# Parallel_CS_V5.net
KiCad netlist of a schematic drawn in EAGLE
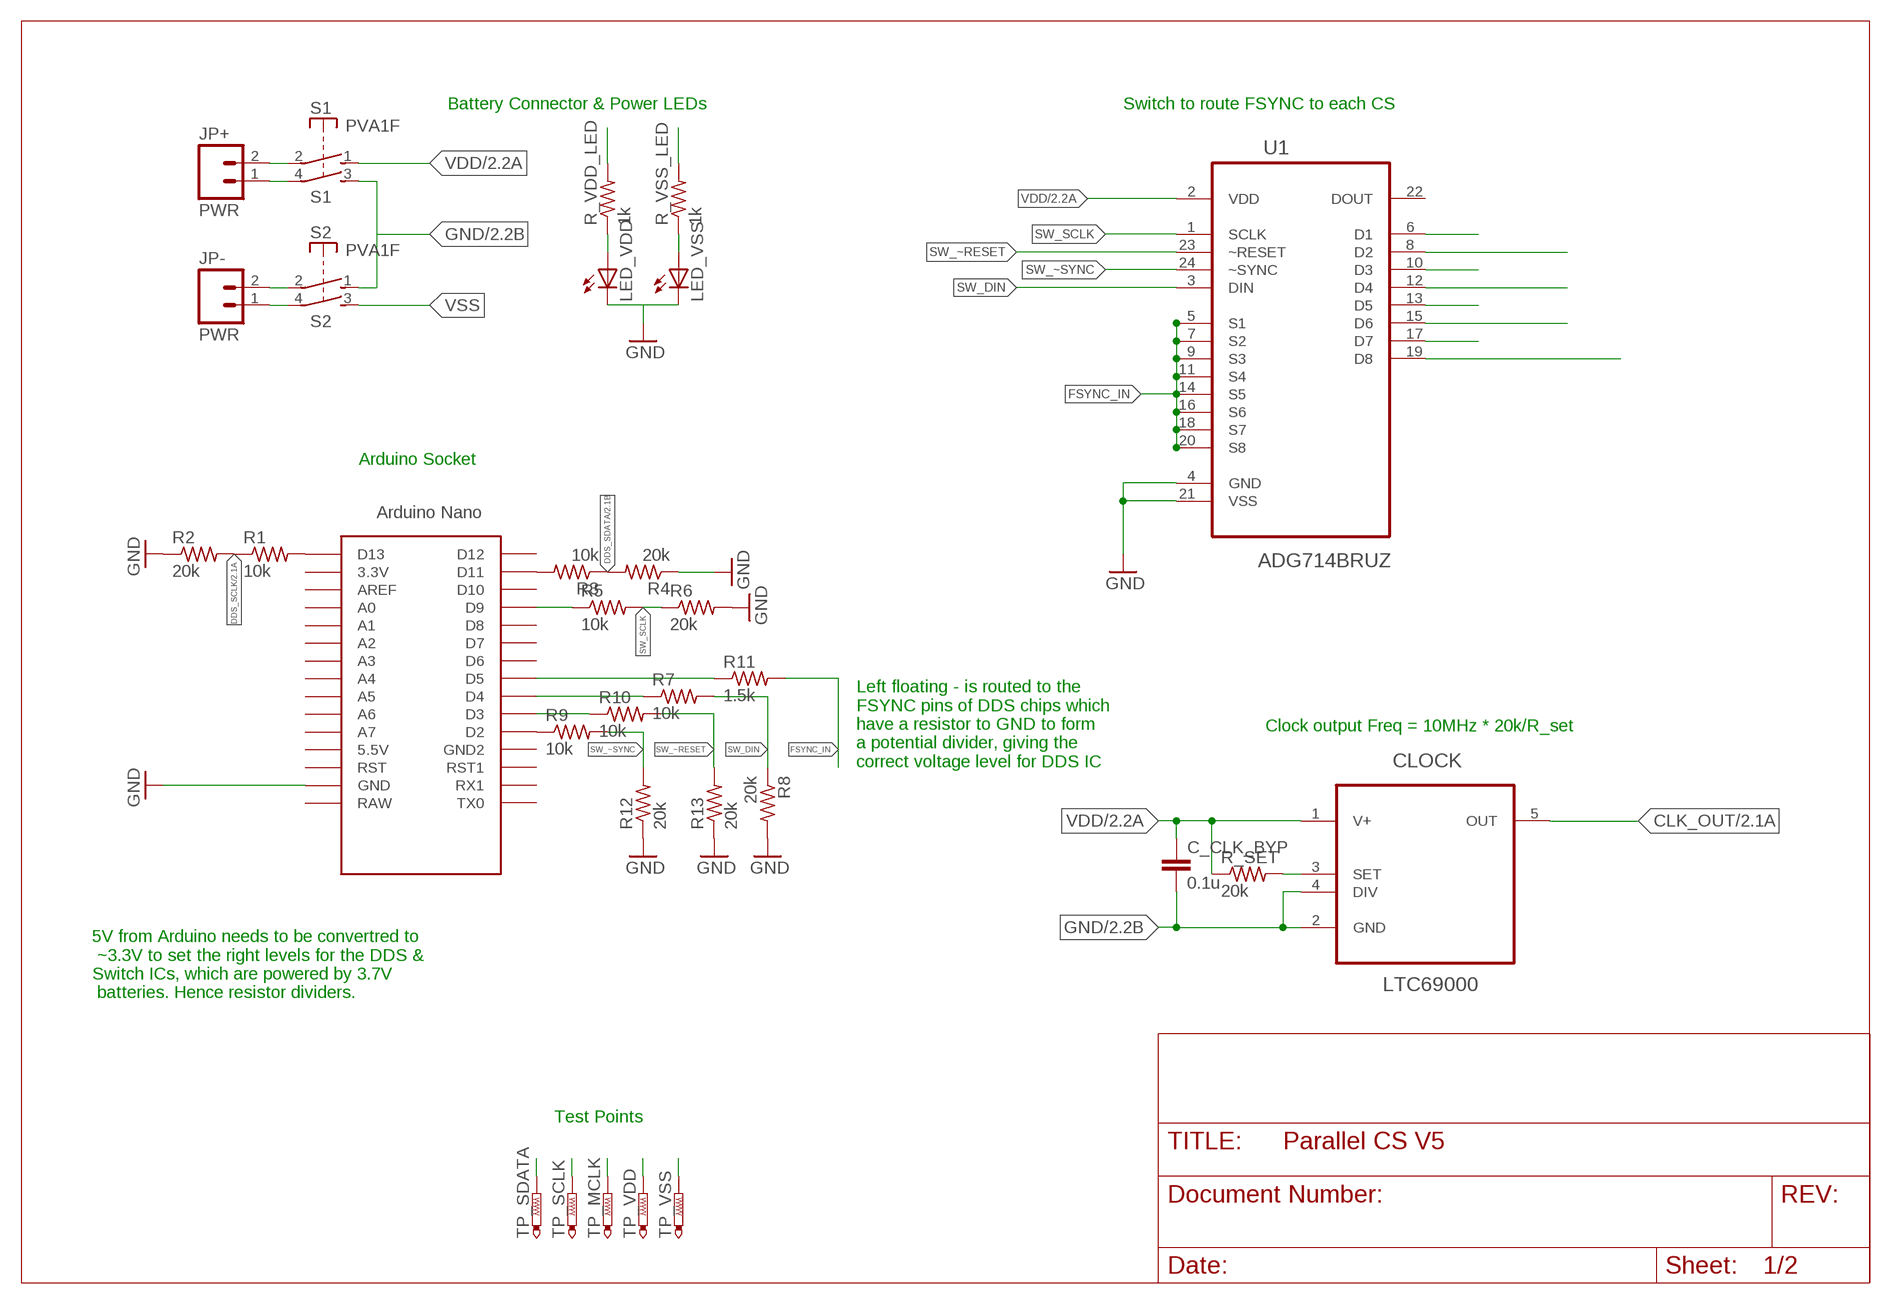
[diagram p0: schematic, sheet 1]
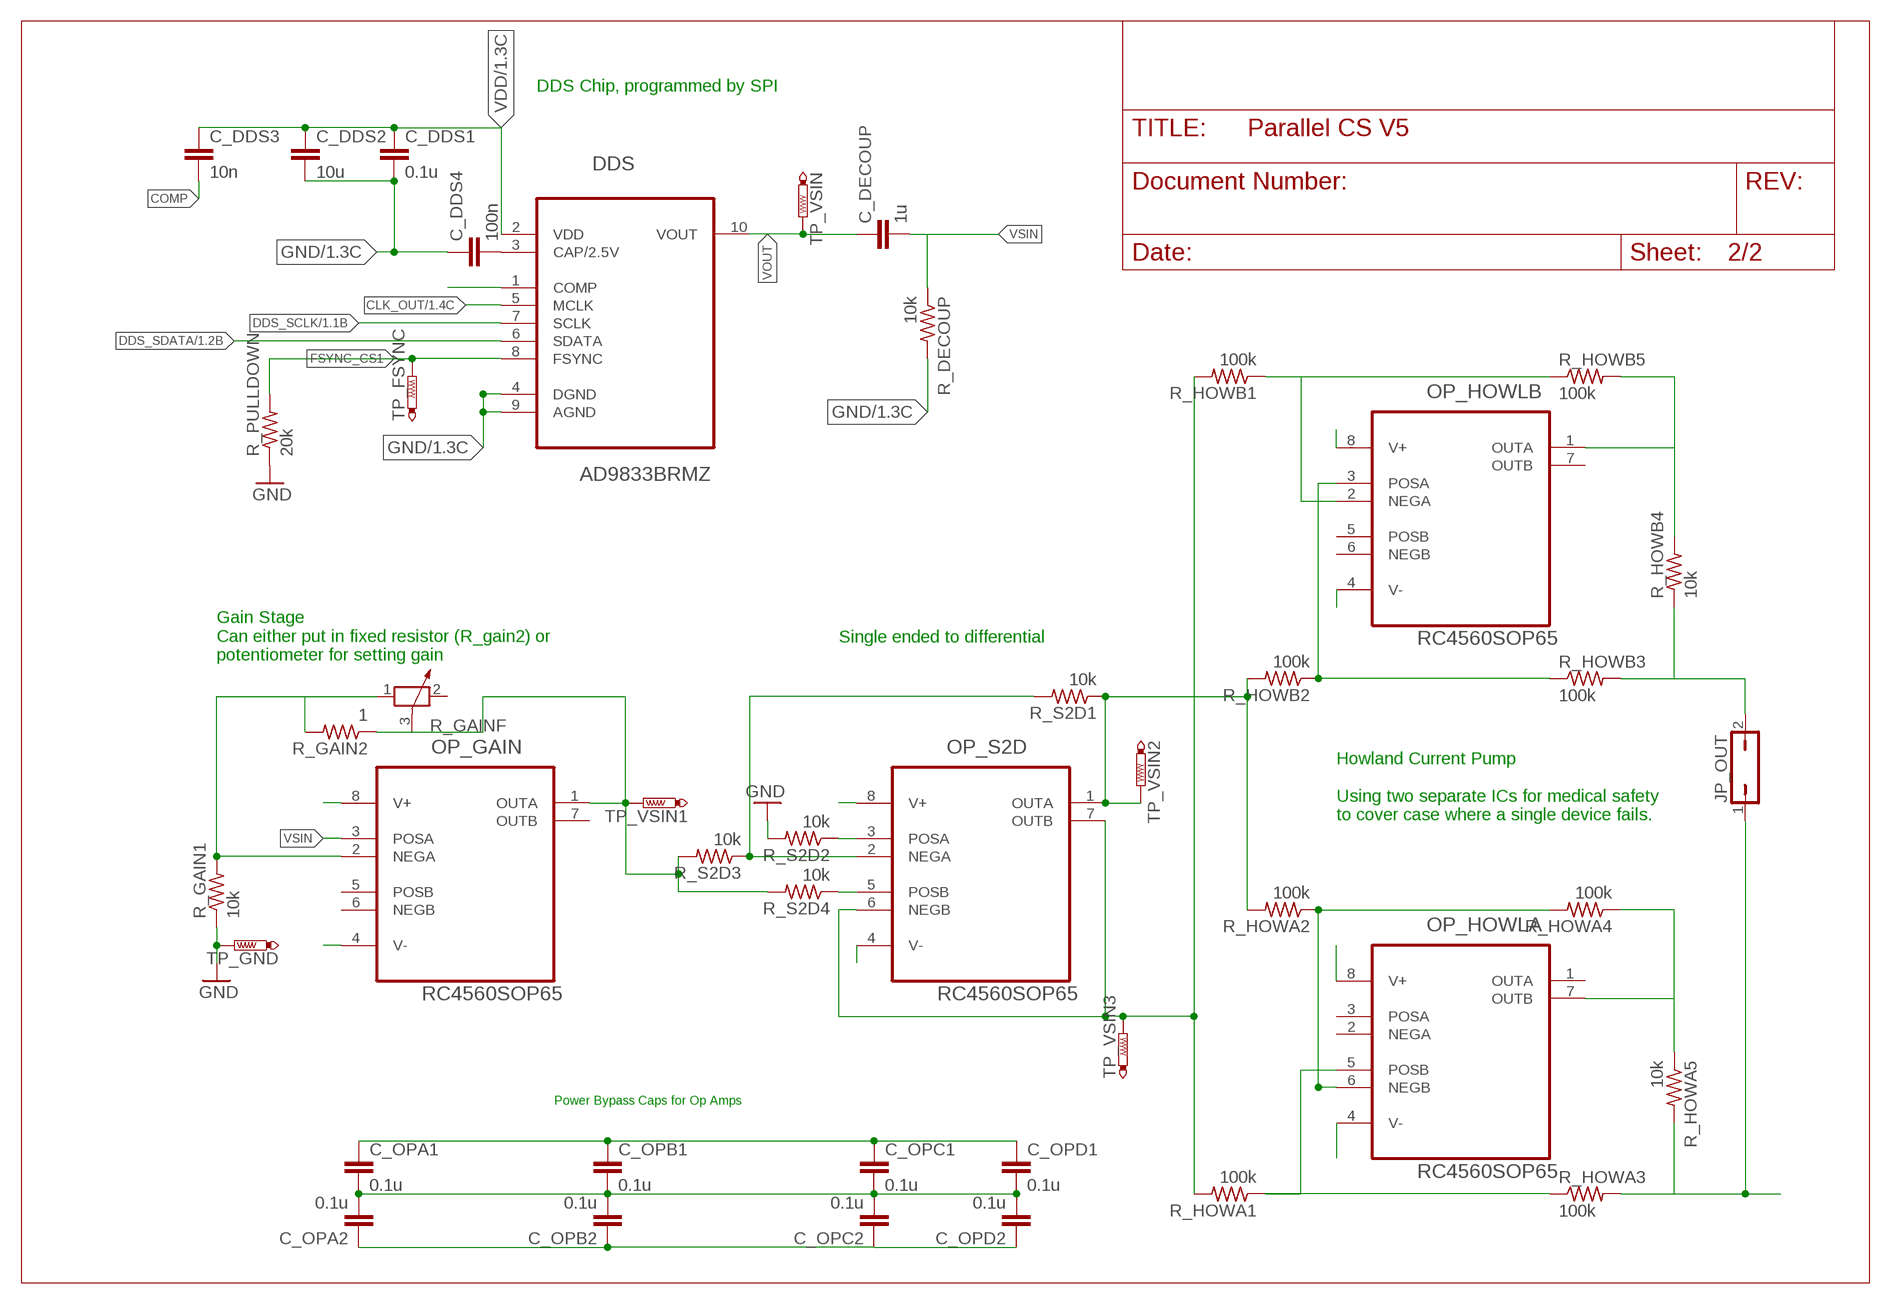
[diagram p1: schematic, sheet 2]

(export (version "E")
  (design (tool "Eeschema 10.0.6"))
  (components
    (comp (ref "C_DDS1")
      (value "0.1u")
      (footprint "eagle-import:C0805")
      (libsource (lib "eagle-import") (part "C-EUC0805"))
    )
    (comp (ref "C_DDS2")
      (value "10u")
      (footprint "eagle-import:C0805")
      (libsource (lib "eagle-import") (part "C-EUC0805"))
    )
    (comp (ref "C_DDS3")
      (value "10n")
      (footprint "eagle-import:C0805")
      (libsource (lib "eagle-import") (part "C-EUC0805"))
    )
    (comp (ref "C_DDS4")
      (value "100n")
      (footprint "eagle-import:C0805")
      (libsource (lib "eagle-import") (part "C-EUC0805"))
    )
    (comp (ref "C_DECOUP")
      (value "1u")
      (footprint "eagle-import:C0805")
      (libsource (lib "eagle-import") (part "C-EUC0805"))
    )
    (comp (ref "C_OPA1")
      (value "0.1u")
      (footprint "eagle-import:C0805")
      (libsource (lib "eagle-import") (part "C-EUC0805"))
    )
    (comp (ref "C_OPA2")
      (value "0.1u")
      (footprint "eagle-import:C0805")
      (libsource (lib "eagle-import") (part "C-EUC0805"))
    )
    (comp (ref "C_OPB1")
      (value "0.1u")
      (footprint "eagle-import:C0805")
      (libsource (lib "eagle-import") (part "C-EUC0805"))
    )
    (comp (ref "C_OPB2")
      (value "0.1u")
      (footprint "eagle-import:C0805")
      (libsource (lib "eagle-import") (part "C-EUC0805"))
    )
    (comp (ref "C_OPC1")
      (value "0.1u")
      (footprint "eagle-import:C0805")
      (libsource (lib "eagle-import") (part "C-EUC0805"))
    )
    (comp (ref "C_OPC2")
      (value "0.1u")
      (footprint "eagle-import:C0805")
      (libsource (lib "eagle-import") (part "C-EUC0805"))
    )
    (comp (ref "C_OPD1")
      (value "0.1u")
      (footprint "eagle-import:C0805")
      (libsource (lib "eagle-import") (part "C-EUC0805"))
    )
    (comp (ref "C_OPD2")
      (value "0.1u")
      (footprint "eagle-import:C0805")
      (libsource (lib "eagle-import") (part "C-EUC0805"))
    )
    (comp (ref "DDS")
      (value "AD9833BRMZ")
      (footprint "eagle-import:SOP50P490X110-10N")
      (libsource (lib "eagle-import") (part "AD9833BRMZ"))
    )
    (comp (ref "JP_OUT")
      (value "JP1Q")
      (footprint "eagle-import:JP1")
      (libsource (lib "eagle-import") (part "JP1Q"))
    )
    (comp (ref "OP_GAIN")
      (value "RC4560SOP65")
      (footprint "eagle-import:SOP65P490X109-8N")
      (libsource (lib "eagle-import") (part "RC4560SOP65"))
    )
    (comp (ref "OP_HOWLA")
      (value "RC4560SOP65")
      (footprint "eagle-import:SOP65P490X109-8N")
      (libsource (lib "eagle-import") (part "RC4560SOP65"))
    )
    (comp (ref "OP_HOWLB")
      (value "RC4560SOP65")
      (footprint "eagle-import:SOP65P490X109-8N")
      (libsource (lib "eagle-import") (part "RC4560SOP65"))
    )
    (comp (ref "OP_S2D")
      (value "RC4560SOP65")
      (footprint "eagle-import:SOP65P490X109-8N")
      (libsource (lib "eagle-import") (part "RC4560SOP65"))
    )
    (comp (ref "R_DECOUP")
      (value "10k")
      (footprint "eagle-import:R0805")
      (libsource (lib "eagle-import") (part "R-US_R0805"))
    )
    (comp (ref "R_GAIN1")
      (value "10k")
      (footprint "eagle-import:R0805")
      (libsource (lib "eagle-import") (part "R-US_R0805"))
    )
    (comp (ref "R_GAIN2")
      (value "1")
      (footprint "eagle-import:R0805")
      (libsource (lib "eagle-import") (part "R-US_R0805"))
    )
    (comp (ref "R_GAINF")
      (value "POTENTIOMETER_PT-10")
      (footprint "eagle-import:PT-10")
      (libsource (lib "eagle-import") (part "POTENTIOMETER_PT-10"))
    )
    (comp (ref "R_HOWA1")
      (value "100k")
      (footprint "eagle-import:R0805")
      (libsource (lib "eagle-import") (part "R-US_R0805"))
    )
    (comp (ref "R_HOWA2")
      (value "100k")
      (footprint "eagle-import:R0805")
      (libsource (lib "eagle-import") (part "R-US_R0805"))
    )
    (comp (ref "R_HOWA3")
      (value "100k")
      (footprint "eagle-import:R0805")
      (libsource (lib "eagle-import") (part "R-US_R0805"))
    )
    (comp (ref "R_HOWA4")
      (value "100k")
      (footprint "eagle-import:R0805")
      (libsource (lib "eagle-import") (part "R-US_R0805"))
    )
    (comp (ref "R_HOWA5")
      (value "10k")
      (footprint "eagle-import:R0805")
      (libsource (lib "eagle-import") (part "R-US_R0805"))
    )
    (comp (ref "R_HOWB1")
      (value "100k")
      (footprint "eagle-import:R0805")
      (libsource (lib "eagle-import") (part "R-US_R0805"))
    )
    (comp (ref "R_HOWB2")
      (value "100k")
      (footprint "eagle-import:R0805")
      (libsource (lib "eagle-import") (part "R-US_R0805"))
    )
    (comp (ref "R_HOWB3")
      (value "100k")
      (footprint "eagle-import:R0805")
      (libsource (lib "eagle-import") (part "R-US_R0805"))
    )
    (comp (ref "R_HOWB4")
      (value "10k")
      (footprint "eagle-import:R0805")
      (libsource (lib "eagle-import") (part "R-US_R0805"))
    )
    (comp (ref "R_HOWB5")
      (value "100k")
      (footprint "eagle-import:R0805")
      (libsource (lib "eagle-import") (part "R-US_R0805"))
    )
    (comp (ref "R_PULLDOWN")
      (value "20k")
      (footprint "eagle-import:R0805")
      (libsource (lib "eagle-import") (part "R-US_R0805"))
    )
    (comp (ref "R_S2D1")
      (value "10k")
      (footprint "eagle-import:R0805")
      (libsource (lib "eagle-import") (part "R-US_R0805"))
    )
    (comp (ref "R_S2D2")
      (value "10k")
      (footprint "eagle-import:R0805")
      (libsource (lib "eagle-import") (part "R-US_R0805"))
    )
    (comp (ref "R_S2D3")
      (value "10k")
      (footprint "eagle-import:R0805")
      (libsource (lib "eagle-import") (part "R-US_R0805"))
    )
    (comp (ref "R_S2D4")
      (value "10k")
      (footprint "eagle-import:R0805")
      (libsource (lib "eagle-import") (part "R-US_R0805"))
    )
    (comp (ref "TP_FSYNC")
      (value "PTR1PAD1-13")
      (footprint "eagle-import:P1-13")
      (libsource (lib "eagle-import") (part "PTR1PAD1-13"))
    )
    (comp (ref "TP_GND")
      (value "PTR1PAD1-13")
      (footprint "eagle-import:P1-13")
      (libsource (lib "eagle-import") (part "PTR1PAD1-13"))
    )
    (comp (ref "TP_VSIN")
      (value "PTR1PAD1-13")
      (footprint "eagle-import:P1-13")
      (libsource (lib "eagle-import") (part "PTR1PAD1-13"))
    )
    (comp (ref "TP_VSIN1")
      (value "PTR1PAD1-13")
      (footprint "eagle-import:P1-13")
      (libsource (lib "eagle-import") (part "PTR1PAD1-13"))
    )
    (comp (ref "TP_VSIN2")
      (value "PTR1PAD1-13")
      (footprint "eagle-import:P1-13")
      (libsource (lib "eagle-import") (part "PTR1PAD1-13"))
    )
    (comp (ref "TP_VSIN3")
      (value "PTR1PAD1-13")
      (footprint "eagle-import:P1-13")
      (libsource (lib "eagle-import") (part "PTR1PAD1-13"))
    )
    (comp (ref "CLOCK")
      (value "LTC69000")
      (footprint "eagle-import:SOT23-5L")
      (libsource (lib "eagle-import") (part "LTC69000"))
    )
    (comp (ref "C_CLK_BYP")
      (value "0.1u")
      (footprint "eagle-import:C0805")
      (libsource (lib "eagle-import") (part "C-EUC0805"))
    )
    (comp (ref "JP+")
      (value "PWR")
      (footprint "eagle-import:JST-2-SMD")
      (libsource (lib "eagle-import") (part "M02-JST-2MM-SMT"))
    )
    (comp (ref "JP-")
      (value "PWR")
      (footprint "eagle-import:JST-2-SMD")
      (libsource (lib "eagle-import") (part "M02-JST-2MM-SMT"))
    )
    (comp (ref "LED_VDD")
      (value "LEDSML0805")
      (footprint "eagle-import:SML0805")
      (libsource (lib "eagle-import") (part "LEDSML0805"))
    )
    (comp (ref "LED_VSS")
      (value "LEDSML0805")
      (footprint "eagle-import:SML0805")
      (libsource (lib "eagle-import") (part "LEDSML0805"))
    )
    (comp (ref "R1")
      (value "10k")
      (footprint "eagle-import:R0805")
      (libsource (lib "eagle-import") (part "resistor_R-US_R0805"))
    )
    (comp (ref "R2")
      (value "20k")
      (footprint "eagle-import:R0805")
      (libsource (lib "eagle-import") (part "resistor_R-US_R0805"))
    )
    (comp (ref "R3")
      (value "10k")
      (footprint "eagle-import:R0805")
      (libsource (lib "eagle-import") (part "resistor_R-US_R0805"))
    )
    (comp (ref "R4")
      (value "20k")
      (footprint "eagle-import:R0805")
      (libsource (lib "eagle-import") (part "resistor_R-US_R0805"))
    )
    (comp (ref "R5")
      (value "10k")
      (footprint "eagle-import:R0805")
      (libsource (lib "eagle-import") (part "resistor_R-US_R0805"))
    )
    (comp (ref "R6")
      (value "20k")
      (footprint "eagle-import:R0805")
      (libsource (lib "eagle-import") (part "resistor_R-US_R0805"))
    )
    (comp (ref "R7")
      (value "10k")
      (footprint "eagle-import:R0805")
      (libsource (lib "eagle-import") (part "resistor_R-US_R0805"))
    )
    (comp (ref "R8")
      (value "20k")
      (footprint "eagle-import:R0805")
      (libsource (lib "eagle-import") (part "resistor_R-US_R0805"))
    )
    (comp (ref "R9")
      (value "10k")
      (footprint "eagle-import:R0805")
      (libsource (lib "eagle-import") (part "resistor_R-US_R0805"))
    )
    (comp (ref "R10")
      (value "10k")
      (footprint "eagle-import:R0805")
      (libsource (lib "eagle-import") (part "resistor_R-US_R0805"))
    )
    (comp (ref "R11")
      (value "1.5k")
      (footprint "eagle-import:R0805")
      (libsource (lib "eagle-import") (part "resistor_R-US_R0805"))
    )
    (comp (ref "R12")
      (value "20k")
      (footprint "eagle-import:R0805")
      (libsource (lib "eagle-import") (part "resistor_R-US_R0805"))
    )
    (comp (ref "R13")
      (value "20k")
      (footprint "eagle-import:R0805")
      (libsource (lib "eagle-import") (part "resistor_R-US_R0805"))
    )
    (comp (ref "R_SET")
      (value "20k")
      (footprint "eagle-import:R0805")
      (libsource (lib "eagle-import") (part "resistor_R-US_R0805"))
    )
    (comp (ref "R_VDD_LED")
      (value "1k")
      (footprint "eagle-import:M0805")
      (libsource (lib "eagle-import") (part "resistor_R-US_M0805"))
    )
    (comp (ref "R_VSS_LED")
      (value "1k")
      (footprint "eagle-import:M0805")
      (libsource (lib "eagle-import") (part "resistor_R-US_M0805"))
    )
    (comp (ref "S1")
      (value "PVA1F")
      (footprint "eagle-import:PVA1F")
      (libsource (lib "eagle-import") (part "PVA1F"))
    )
    (comp (ref "S2")
      (value "PVA1F")
      (footprint "eagle-import:PVA1F")
      (libsource (lib "eagle-import") (part "PVA1F"))
    )
    (comp (ref "TP_MCLK")
      (value "PTR1PAD1-13")
      (footprint "eagle-import:P1-13")
      (libsource (lib "eagle-import") (part "PTR1PAD1-13"))
    )
    (comp (ref "TP_SCLK")
      (value "PTR1PAD1-13")
      (footprint "eagle-import:P1-13")
      (libsource (lib "eagle-import") (part "PTR1PAD1-13"))
    )
    (comp (ref "TP_SDATA")
      (value "PTR1PAD1-13")
      (footprint "eagle-import:P1-13")
      (libsource (lib "eagle-import") (part "PTR1PAD1-13"))
    )
    (comp (ref "TP_VDD")
      (value "PTR1PAD1-13")
      (footprint "eagle-import:P1-13")
      (libsource (lib "eagle-import") (part "PTR1PAD1-13"))
    )
    (comp (ref "TP_VSS")
      (value "PTR1PAD1-13")
      (footprint "eagle-import:P1-13")
      (libsource (lib "eagle-import") (part "PTR1PAD1-13"))
    )
    (comp (ref "U$1")
      (value "NANO")
      (footprint "eagle-import:NANO")
      (libsource (lib "eagle-import") (part "NANO"))
    )
    (comp (ref "U1")
      (value "ADG714BRUZ")
      (footprint "eagle-import:SOP65P640X120-24N")
      (libsource (lib "eagle-import") (part "ADG714BRUZ"))
    )
  )
  (nets
    (net (code "1") (name "CLK_OUT") (class "Default")
      (node (ref "CLOCK") (pin "5") (pinfunction "OUT_5") (pintype "output"))
      (node (ref "DDS") (pin "5") (pinfunction "MCLK_5") (pintype "input"))
      (node (ref "TP_MCLK") (pin "TP") (pinfunction "TP_TP") (pintype "input"))
    )
    (net (code "2") (name "COMP") (class "Default")
      (node (ref "C_DDS3") (pin "2") (pinfunction "2_2") (pintype "passive"))
      (node (ref "DDS") (pin "1") (pinfunction "COMP_1") (pintype "passive"))
    )
    (net (code "3") (name "DDS_SCLK") (class "Default")
      (node (ref "DDS") (pin "7") (pinfunction "SCLK_7") (pintype "input"))
      (node (ref "R1") (pin "1") (pinfunction "1_1") (pintype "passive"))
      (node (ref "R2") (pin "2") (pinfunction "2_2") (pintype "passive"))
      (node (ref "TP_SCLK") (pin "TP") (pinfunction "TP_TP") (pintype "input"))
    )
    (net (code "4") (name "DDS_SDATA") (class "Default")
      (node (ref "DDS") (pin "6") (pinfunction "SDATA_6") (pintype "input"))
      (node (ref "R3") (pin "1") (pinfunction "1_1") (pintype "passive"))
      (node (ref "R4") (pin "2") (pinfunction "2_2") (pintype "passive"))
      (node (ref "TP_SDATA") (pin "TP") (pinfunction "TP_TP") (pintype "input"))
    )
    (net (code "5") (name "FSYNC_CS1") (class "Default")
      (node (ref "DDS") (pin "8") (pinfunction "FSYNC_8") (pintype "input"))
      (node (ref "R_PULLDOWN") (pin "2") (pinfunction "2_2") (pintype "passive"))
      (node (ref "TP_FSYNC") (pin "TP") (pinfunction "TP_TP") (pintype "input"))
      (node (ref "U1") (pin "6") (pinfunction "D1_6") (pintype "bidirectional"))
    )
    (net (code "6") (name "FSYNC_IN") (class "Default")
      (node (ref "R11") (pin "2") (pinfunction "2_2") (pintype "passive"))
      (node (ref "U1") (pin "11") (pinfunction "S4_11") (pintype "bidirectional"))
      (node (ref "U1") (pin "14") (pinfunction "S5_14") (pintype "bidirectional"))
      (node (ref "U1") (pin "16") (pinfunction "S6_16") (pintype "bidirectional"))
      (node (ref "U1") (pin "18") (pinfunction "S7_18") (pintype "bidirectional"))
      (node (ref "U1") (pin "20") (pinfunction "S8_20") (pintype "bidirectional"))
      (node (ref "U1") (pin "5") (pinfunction "S1_5") (pintype "bidirectional"))
      (node (ref "U1") (pin "7") (pinfunction "S2_7") (pintype "bidirectional"))
      (node (ref "U1") (pin "9") (pinfunction "S3_9") (pintype "bidirectional"))
    )
    (net (code "7") (name "GND") (class "Default")
      (node (ref "CLOCK") (pin "2") (pinfunction "GND_2") (pintype "passive"))
      (node (ref "CLOCK") (pin "4") (pinfunction "DIV_4") (pintype "input"))
      (node (ref "C_CLK_BYP") (pin "2") (pinfunction "2_2") (pintype "passive"))
      (node (ref "C_DDS1") (pin "2") (pinfunction "2_2") (pintype "passive"))
      (node (ref "C_DDS2") (pin "2") (pinfunction "2_2") (pintype "passive"))
      (node (ref "C_DDS4") (pin "1") (pinfunction "1_1") (pintype "passive"))
      (node (ref "C_OPA1") (pin "2") (pinfunction "2_2") (pintype "passive"))
      (node (ref "C_OPA2") (pin "2") (pinfunction "2_2") (pintype "passive"))
      (node (ref "C_OPB1") (pin "2") (pinfunction "2_2") (pintype "passive"))
      (node (ref "C_OPB2") (pin "2") (pinfunction "2_2") (pintype "passive"))
      (node (ref "C_OPC1") (pin "2") (pinfunction "2_2") (pintype "passive"))
      (node (ref "C_OPC2") (pin "2") (pinfunction "2_2") (pintype "passive"))
      (node (ref "C_OPD1") (pin "2") (pinfunction "2_2") (pintype "passive"))
      (node (ref "C_OPD2") (pin "2") (pinfunction "2_2") (pintype "passive"))
      (node (ref "DDS") (pin "4") (pinfunction "DGND_4") (pintype "passive"))
      (node (ref "DDS") (pin "9") (pinfunction "AGND_9") (pintype "passive"))
      (node (ref "LED_VDD") (pin "C") (pinfunction "C_C") (pintype "passive"))
      (node (ref "LED_VSS") (pin "C") (pinfunction "C_C") (pintype "passive"))
      (node (ref "R12") (pin "1") (pinfunction "1_1") (pintype "passive"))
      (node (ref "R13") (pin "1") (pinfunction "1_1") (pintype "passive"))
      (node (ref "R2") (pin "1") (pinfunction "1_1") (pintype "passive"))
      (node (ref "R4") (pin "1") (pinfunction "1_1") (pintype "passive"))
      (node (ref "R6") (pin "2") (pinfunction "2_2") (pintype "passive"))
      (node (ref "R8") (pin "2") (pinfunction "2_2") (pintype "passive"))
      (node (ref "R_DECOUP") (pin "2") (pinfunction "2_2") (pintype "passive"))
      (node (ref "R_GAIN1") (pin "1") (pinfunction "1_1") (pintype "passive"))
      (node (ref "R_PULLDOWN") (pin "1") (pinfunction "1_1") (pintype "passive"))
      (node (ref "R_S2D2") (pin "2") (pinfunction "2_2") (pintype "passive"))
      (node (ref "S1") (pin "3") (pinfunction "S_3") (pintype "passive"))
      (node (ref "S2") (pin "1") (pinfunction "S_1") (pintype "passive"))
      (node (ref "TP_GND") (pin "TP") (pinfunction "TP_TP") (pintype "input"))
      (node (ref "U$1") (pin "GND") (pinfunction "GND_GND") (pintype "bidirectional"))
      (node (ref "U1") (pin "21") (pinfunction "VSS_21") (pintype "power_in"))
      (node (ref "U1") (pin "4") (pinfunction "GND_4") (pintype "passive"))
    )
    (net (code "8") (name "Net-(CLOCK-SET)") (class "Default")
      (node (ref "CLOCK") (pin "3") (pinfunction "SET_3") (pintype "input"))
      (node (ref "R_SET") (pin "2") (pinfunction "2_2") (pintype "passive"))
    )
    (net (code "9") (name "Net-(DDS-CAP{slash}2.5V)") (class "Default")
      (node (ref "C_DDS4") (pin "2") (pinfunction "2_2") (pintype "passive"))
      (node (ref "DDS") (pin "3") (pinfunction "CAP/2.5V_3") (pintype "passive"))
    )
    (net (code "10") (name "Net-(JP_OUT-Pad1)") (class "Default")
      (node (ref "JP_OUT") (pin "1") (pinfunction "1_1") (pintype "passive"))
      (node (ref "R_HOWA3") (pin "2") (pinfunction "2_2") (pintype "passive"))
      (node (ref "R_HOWA5") (pin "2") (pinfunction "2_2") (pintype "passive"))
    )
    (net (code "11") (name "Net-(JP_OUT-Pad2)") (class "Default")
      (node (ref "JP_OUT") (pin "2") (pinfunction "2_2") (pintype "passive"))
      (node (ref "R_HOWB3") (pin "2") (pinfunction "2_2") (pintype "passive"))
      (node (ref "R_HOWB4") (pin "1") (pinfunction "1_1") (pintype "passive"))
    )
    (net (code "12") (name "Net-(LED_VDD-PadA)") (class "Default")
      (node (ref "LED_VDD") (pin "A") (pinfunction "A_A") (pintype "passive"))
      (node (ref "R_VDD_LED") (pin "1") (pinfunction "1_1") (pintype "passive"))
    )
    (net (code "13") (name "Net-(LED_VSS-PadA)") (class "Default")
      (node (ref "LED_VSS") (pin "A") (pinfunction "A_A") (pintype "passive"))
      (node (ref "R_VSS_LED") (pin "1") (pinfunction "1_1") (pintype "passive"))
    )
    (net (code "14") (name "Net-(OP_GAIN-NEGA)") (class "Default")
      (node (ref "OP_GAIN") (pin "2") (pinfunction "NEGA_2") (pintype "input"))
      (node (ref "R_GAIN1") (pin "2") (pinfunction "2_2") (pintype "passive"))
      (node (ref "R_GAIN2") (pin "2") (pinfunction "2_2") (pintype "passive"))
      (node (ref "R_GAINF") (pin "1") (pinfunction "1_1") (pintype "passive"))
    )
    (net (code "15") (name "Net-(OP_GAIN-OUTA)") (class "Default")
      (node (ref "OP_GAIN") (pin "1") (pinfunction "OUTA_1") (pintype "output"))
      (node (ref "R_GAIN2") (pin "1") (pinfunction "1_1") (pintype "passive"))
      (node (ref "R_GAINF") (pin "3") (pinfunction "3_3") (pintype "passive"))
      (node (ref "R_S2D3") (pin "2") (pinfunction "2_2") (pintype "passive"))
      (node (ref "R_S2D4") (pin "2") (pinfunction "2_2") (pintype "passive"))
      (node (ref "TP_VSIN1") (pin "TP") (pinfunction "TP_TP") (pintype "input"))
    )
    (net (code "16") (name "Net-(OP_HOWLA-NEGB)") (class "Default")
      (node (ref "OP_HOWLA") (pin "6") (pinfunction "NEGB_6") (pintype "input"))
      (node (ref "R_HOWA2") (pin "1") (pinfunction "1_1") (pintype "passive"))
      (node (ref "R_HOWA4") (pin "2") (pinfunction "2_2") (pintype "passive"))
    )
    (net (code "17") (name "Net-(OP_HOWLA-OUTB)") (class "Default")
      (node (ref "OP_HOWLA") (pin "7") (pinfunction "OUTB_7") (pintype "output"))
      (node (ref "R_HOWA4") (pin "1") (pinfunction "1_1") (pintype "passive"))
      (node (ref "R_HOWA5") (pin "1") (pinfunction "1_1") (pintype "passive"))
    )
    (net (code "18") (name "Net-(OP_HOWLA-POSB)") (class "Default")
      (node (ref "OP_HOWLA") (pin "5") (pinfunction "POSB_5") (pintype "input"))
      (node (ref "R_HOWA1") (pin "1") (pinfunction "1_1") (pintype "passive"))
      (node (ref "R_HOWA3") (pin "1") (pinfunction "1_1") (pintype "passive"))
    )
    (net (code "19") (name "Net-(OP_HOWLB-NEGA)") (class "Default")
      (node (ref "OP_HOWLB") (pin "2") (pinfunction "NEGA_2") (pintype "input"))
      (node (ref "R_HOWB1") (pin "1") (pinfunction "1_1") (pintype "passive"))
      (node (ref "R_HOWB5") (pin "1") (pinfunction "1_1") (pintype "passive"))
    )
    (net (code "20") (name "Net-(OP_HOWLB-OUTA)") (class "Default")
      (node (ref "OP_HOWLB") (pin "1") (pinfunction "OUTA_1") (pintype "output"))
      (node (ref "R_HOWB4") (pin "2") (pinfunction "2_2") (pintype "passive"))
      (node (ref "R_HOWB5") (pin "2") (pinfunction "2_2") (pintype "passive"))
    )
    (net (code "21") (name "Net-(OP_HOWLB-POSA)") (class "Default")
      (node (ref "OP_HOWLB") (pin "3") (pinfunction "POSA_3") (pintype "input"))
      (node (ref "R_HOWB2") (pin "1") (pinfunction "1_1") (pintype "passive"))
      (node (ref "R_HOWB3") (pin "1") (pinfunction "1_1") (pintype "passive"))
    )
    (net (code "22") (name "Net-(OP_S2D-NEGA)") (class "Default")
      (node (ref "OP_S2D") (pin "2") (pinfunction "NEGA_2") (pintype "input"))
      (node (ref "R_S2D1") (pin "2") (pinfunction "2_2") (pintype "passive"))
      (node (ref "R_S2D3") (pin "1") (pinfunction "1_1") (pintype "passive"))
    )
    (net (code "23") (name "Net-(OP_S2D-NEGB)") (class "Default")
      (node (ref "OP_S2D") (pin "6") (pinfunction "NEGB_6") (pintype "input"))
      (node (ref "OP_S2D") (pin "7") (pinfunction "OUTB_7") (pintype "output"))
      (node (ref "R_HOWA1") (pin "2") (pinfunction "2_2") (pintype "passive"))
      (node (ref "R_HOWB1") (pin "2") (pinfunction "2_2") (pintype "passive"))
      (node (ref "TP_VSIN3") (pin "TP") (pinfunction "TP_TP") (pintype "input"))
    )
    (net (code "24") (name "Net-(OP_S2D-OUTA)") (class "Default")
      (node (ref "OP_S2D") (pin "1") (pinfunction "OUTA_1") (pintype "output"))
      (node (ref "R_HOWA2") (pin "2") (pinfunction "2_2") (pintype "passive"))
      (node (ref "R_HOWB2") (pin "2") (pinfunction "2_2") (pintype "passive"))
      (node (ref "R_S2D1") (pin "1") (pinfunction "1_1") (pintype "passive"))
      (node (ref "TP_VSIN2") (pin "TP") (pinfunction "TP_TP") (pintype "input"))
    )
    (net (code "25") (name "Net-(OP_S2D-POSA)") (class "Default")
      (node (ref "OP_S2D") (pin "3") (pinfunction "POSA_3") (pintype "input"))
      (node (ref "R_S2D2") (pin "1") (pinfunction "1_1") (pintype "passive"))
    )
    (net (code "26") (name "Net-(OP_S2D-POSB)") (class "Default")
      (node (ref "OP_S2D") (pin "5") (pinfunction "POSB_5") (pintype "input"))
      (node (ref "R_S2D4") (pin "1") (pinfunction "1_1") (pintype "passive"))
    )
    (net (code "27") (name "Net-(R1-Pad2)") (class "Default")
      (node (ref "R1") (pin "2") (pinfunction "2_2") (pintype "passive"))
      (node (ref "U$1") (pin "D13") (pinfunction "D13_D13") (pintype "bidirectional"))
    )
    (net (code "28") (name "Net-(R3-Pad2)") (class "Default")
      (node (ref "R3") (pin "2") (pinfunction "2_2") (pintype "passive"))
      (node (ref "U$1") (pin "D11") (pinfunction "D11_D11") (pintype "bidirectional"))
    )
    (net (code "29") (name "Net-(R5-Pad1)") (class "Default")
      (node (ref "R5") (pin "1") (pinfunction "1_1") (pintype "passive"))
      (node (ref "U$1") (pin "D9") (pinfunction "D9_D9") (pintype "bidirectional"))
    )
    (net (code "30") (name "Net-(R7-Pad1)") (class "Default")
      (node (ref "R7") (pin "1") (pinfunction "1_1") (pintype "passive"))
      (node (ref "U$1") (pin "D4") (pinfunction "D4_D4") (pintype "bidirectional"))
    )
    (net (code "31") (name "Net-(R9-Pad1)") (class "Default")
      (node (ref "R9") (pin "1") (pinfunction "1_1") (pintype "passive"))
      (node (ref "U$1") (pin "D2") (pinfunction "D2_D2") (pintype "bidirectional"))
    )
    (net (code "32") (name "Net-(R10-Pad1)") (class "Default")
      (node (ref "R10") (pin "1") (pinfunction "1_1") (pintype "passive"))
      (node (ref "U$1") (pin "D3") (pinfunction "D3_D3") (pintype "bidirectional"))
    )
    (net (code "33") (name "Net-(R11-Pad1)") (class "Default")
      (node (ref "R11") (pin "1") (pinfunction "1_1") (pintype "passive"))
      (node (ref "U$1") (pin "D5") (pinfunction "D5_D5") (pintype "bidirectional"))
    )
    (net (code "34") (name "Net-(S1A-P)") (class "Default")
      (node (ref "JP+") (pin "2") (pinfunction "2_2") (pintype "passive"))
      (node (ref "S1") (pin "2") (pinfunction "P_2") (pintype "passive"))
    )
    (net (code "35") (name "Net-(S1B-P)") (class "Default")
      (node (ref "JP+") (pin "1") (pinfunction "1_1") (pintype "passive"))
      (node (ref "S1") (pin "4") (pinfunction "P_4") (pintype "passive"))
    )
    (net (code "36") (name "Net-(S2A-P)") (class "Default")
      (node (ref "JP-") (pin "2") (pinfunction "2_2") (pintype "passive"))
      (node (ref "S2") (pin "2") (pinfunction "P_2") (pintype "passive"))
    )
    (net (code "37") (name "Net-(S2B-P)") (class "Default")
      (node (ref "JP-") (pin "1") (pinfunction "1_1") (pintype "passive"))
      (node (ref "S2") (pin "4") (pinfunction "P_4") (pintype "passive"))
    )
    (net (code "38") (name "SW_DIN") (class "Default")
      (node (ref "R7") (pin "2") (pinfunction "2_2") (pintype "passive"))
      (node (ref "R8") (pin "1") (pinfunction "1_1") (pintype "passive"))
      (node (ref "U1") (pin "3") (pinfunction "DIN_3") (pintype "input"))
    )
    (net (code "39") (name "SW_SCLK") (class "Default")
      (node (ref "R5") (pin "2") (pinfunction "2_2") (pintype "passive"))
      (node (ref "R6") (pin "1") (pinfunction "1_1") (pintype "passive"))
      (node (ref "U1") (pin "1") (pinfunction "SCLK_1") (pintype "input"))
    )
    (net (code "40") (name "SW_~{RESET}") (class "Default")
      (node (ref "R10") (pin "2") (pinfunction "2_2") (pintype "passive"))
      (node (ref "R13") (pin "2") (pinfunction "2_2") (pintype "passive"))
      (node (ref "U1") (pin "23") (pinfunction "~{RESET}_23") (pintype "input"))
    )
    (net (code "41") (name "SW_~{SYNC}") (class "Default")
      (node (ref "R12") (pin "2") (pinfunction "2_2") (pintype "passive"))
      (node (ref "R9") (pin "2") (pinfunction "2_2") (pintype "passive"))
      (node (ref "U1") (pin "24") (pinfunction "~{SYNC}_24") (pintype "input"))
    )
    (net (code "42") (name "VDD") (class "Default")
      (node (ref "CLOCK") (pin "1") (pinfunction "V+_1") (pintype "power_in"))
      (node (ref "C_CLK_BYP") (pin "1") (pinfunction "1_1") (pintype "passive"))
      (node (ref "C_DDS1") (pin "1") (pinfunction "1_1") (pintype "passive"))
      (node (ref "C_DDS2") (pin "1") (pinfunction "1_1") (pintype "passive"))
      (node (ref "C_DDS3") (pin "1") (pinfunction "1_1") (pintype "passive"))
      (node (ref "C_OPA1") (pin "1") (pinfunction "1_1") (pintype "passive"))
      (node (ref "C_OPB1") (pin "1") (pinfunction "1_1") (pintype "passive"))
      (node (ref "C_OPC1") (pin "1") (pinfunction "1_1") (pintype "passive"))
      (node (ref "C_OPD1") (pin "1") (pinfunction "1_1") (pintype "passive"))
      (node (ref "DDS") (pin "2") (pinfunction "VDD_2") (pintype "power_in"))
      (node (ref "OP_GAIN") (pin "8") (pinfunction "V+_8") (pintype "power_in"))
      (node (ref "OP_HOWLA") (pin "8") (pinfunction "V+_8") (pintype "power_in"))
      (node (ref "OP_HOWLB") (pin "8") (pinfunction "V+_8") (pintype "power_in"))
      (node (ref "OP_S2D") (pin "8") (pinfunction "V+_8") (pintype "power_in"))
      (node (ref "R_SET") (pin "1") (pinfunction "1_1") (pintype "passive"))
      (node (ref "R_VDD_LED") (pin "2") (pinfunction "2_2") (pintype "passive"))
      (node (ref "S1") (pin "1") (pinfunction "S_1") (pintype "passive"))
      (node (ref "TP_VDD") (pin "TP") (pinfunction "TP_TP") (pintype "input"))
      (node (ref "U1") (pin "2") (pinfunction "VDD_2") (pintype "power_in"))
    )
    (net (code "43") (name "VOUT") (class "Default")
      (node (ref "C_DECOUP") (pin "1") (pinfunction "1_1") (pintype "passive"))
      (node (ref "DDS") (pin "10") (pinfunction "VOUT_10") (pintype "output"))
      (node (ref "TP_VSIN") (pin "TP") (pinfunction "TP_TP") (pintype "input"))
    )
    (net (code "44") (name "VSIN") (class "Default")
      (node (ref "C_DECOUP") (pin "2") (pinfunction "2_2") (pintype "passive"))
      (node (ref "OP_GAIN") (pin "3") (pinfunction "POSA_3") (pintype "input"))
      (node (ref "R_DECOUP") (pin "1") (pinfunction "1_1") (pintype "passive"))
    )
    (net (code "45") (name "VSS") (class "Default")
      (node (ref "C_OPA2") (pin "1") (pinfunction "1_1") (pintype "passive"))
      (node (ref "C_OPB2") (pin "1") (pinfunction "1_1") (pintype "passive"))
      (node (ref "C_OPC2") (pin "1") (pinfunction "1_1") (pintype "passive"))
      (node (ref "C_OPD2") (pin "1") (pinfunction "1_1") (pintype "passive"))
      (node (ref "OP_GAIN") (pin "4") (pinfunction "V-_4") (pintype "power_in"))
      (node (ref "OP_HOWLA") (pin "4") (pinfunction "V-_4") (pintype "power_in"))
      (node (ref "OP_HOWLB") (pin "4") (pinfunction "V-_4") (pintype "power_in"))
      (node (ref "OP_S2D") (pin "4") (pinfunction "V-_4") (pintype "power_in"))
      (node (ref "R_VSS_LED") (pin "2") (pinfunction "2_2") (pintype "passive"))
      (node (ref "S2") (pin "3") (pinfunction "S_3") (pintype "passive"))
      (node (ref "TP_VSS") (pin "TP") (pinfunction "TP_TP") (pintype "input"))
    )
    (net (code "46") (name "unconnected-(OP_GAIN-NEGB-Pad6)") (class "Default")
      (node (ref "OP_GAIN") (pin "6") (pinfunction "NEGB_6") (pintype "input"))
    )
    (net (code "47") (name "unconnected-(OP_GAIN-OUTB-Pad7)") (class "Default")
      (node (ref "OP_GAIN") (pin "7") (pinfunction "OUTB_7") (pintype "output"))
    )
    (net (code "48") (name "unconnected-(OP_GAIN-POSB-Pad5)") (class "Default")
      (node (ref "OP_GAIN") (pin "5") (pinfunction "POSB_5") (pintype "input"))
    )
    (net (code "49") (name "unconnected-(OP_HOWLA-NEGA-Pad2)") (class "Default")
      (node (ref "OP_HOWLA") (pin "2") (pinfunction "NEGA_2") (pintype "input"))
    )
    (net (code "50") (name "unconnected-(OP_HOWLA-OUTA-Pad1)") (class "Default")
      (node (ref "OP_HOWLA") (pin "1") (pinfunction "OUTA_1") (pintype "output"))
    )
    (net (code "51") (name "unconnected-(OP_HOWLA-POSA-Pad3)") (class "Default")
      (node (ref "OP_HOWLA") (pin "3") (pinfunction "POSA_3") (pintype "input"))
    )
    (net (code "52") (name "unconnected-(OP_HOWLB-NEGB-Pad6)") (class "Default")
      (node (ref "OP_HOWLB") (pin "6") (pinfunction "NEGB_6") (pintype "input"))
    )
    (net (code "53") (name "unconnected-(OP_HOWLB-OUTB-Pad7)") (class "Default")
      (node (ref "OP_HOWLB") (pin "7") (pinfunction "OUTB_7") (pintype "output"))
    )
    (net (code "54") (name "unconnected-(OP_HOWLB-POSB-Pad5)") (class "Default")
      (node (ref "OP_HOWLB") (pin "5") (pinfunction "POSB_5") (pintype "input"))
    )
    (net (code "55") (name "unconnected-(R_GAINF-Pad2)") (class "Default")
      (node (ref "R_GAINF") (pin "2") (pinfunction "2_2") (pintype "passive"))
    )
    (net (code "56") (name "unconnected-(U$1-5.5V-Pad5V)") (class "Default")
      (node (ref "U$1") (pin "5V") (pinfunction "5.5V_5V") (pintype "bidirectional"))
    )
    (net (code "57") (name "unconnected-(U$1-GND2-PadGND1)") (class "Default")
      (node (ref "U$1") (pin "GND1") (pinfunction "GND2_GND1") (pintype "bidirectional"))
    )
    (net (code "58") (name "unconnected-(U$1-Pad3.3V)") (class "Default")
      (node (ref "U$1") (pin "3.3V") (pinfunction "3.3V_3.3V") (pintype "bidirectional"))
    )
    (net (code "59") (name "unconnected-(U$1-PadA0)") (class "Default")
      (node (ref "U$1") (pin "A0") (pinfunction "A0_A0") (pintype "bidirectional"))
    )
    (net (code "60") (name "unconnected-(U$1-PadA1)") (class "Default")
      (node (ref "U$1") (pin "A1") (pinfunction "A1_A1") (pintype "bidirectional"))
    )
    (net (code "61") (name "unconnected-(U$1-PadA2)") (class "Default")
      (node (ref "U$1") (pin "A2") (pinfunction "A2_A2") (pintype "bidirectional"))
    )
    (net (code "62") (name "unconnected-(U$1-PadA3)") (class "Default")
      (node (ref "U$1") (pin "A3") (pinfunction "A3_A3") (pintype "bidirectional"))
    )
    (net (code "63") (name "unconnected-(U$1-PadA4)") (class "Default")
      (node (ref "U$1") (pin "A4") (pinfunction "A4_A4") (pintype "bidirectional"))
    )
    (net (code "64") (name "unconnected-(U$1-PadA5)") (class "Default")
      (node (ref "U$1") (pin "A5") (pinfunction "A5_A5") (pintype "bidirectional"))
    )
    (net (code "65") (name "unconnected-(U$1-PadA6)") (class "Default")
      (node (ref "U$1") (pin "A6") (pinfunction "A6_A6") (pintype "bidirectional"))
    )
    (net (code "66") (name "unconnected-(U$1-PadA7)") (class "Default")
      (node (ref "U$1") (pin "A7") (pinfunction "A7_A7") (pintype "bidirectional"))
    )
    (net (code "67") (name "unconnected-(U$1-PadAREF)") (class "Default")
      (node (ref "U$1") (pin "AREF") (pinfunction "AREF_AREF") (pintype "bidirectional"))
    )
    (net (code "68") (name "unconnected-(U$1-PadD6)") (class "Default")
      (node (ref "U$1") (pin "D6") (pinfunction "D6_D6") (pintype "bidirectional"))
    )
    (net (code "69") (name "unconnected-(U$1-PadD7)") (class "Default")
      (node (ref "U$1") (pin "D7") (pinfunction "D7_D7") (pintype "bidirectional"))
    )
    (net (code "70") (name "unconnected-(U$1-PadD8)") (class "Default")
      (node (ref "U$1") (pin "D8") (pinfunction "D8_D8") (pintype "bidirectional"))
    )
    (net (code "71") (name "unconnected-(U$1-PadD10)") (class "Default")
      (node (ref "U$1") (pin "D10") (pinfunction "D10_D10") (pintype "bidirectional"))
    )
    (net (code "72") (name "unconnected-(U$1-PadD12)") (class "Default")
      (node (ref "U$1") (pin "D12") (pinfunction "D12_D12") (pintype "bidirectional"))
    )
    (net (code "73") (name "unconnected-(U$1-PadICSP1)") (class "Default")
      (node (ref "U$1") (pin "ICSP1") (pinfunction "ICSP1_ICSP1") (pintype "bidirectional"))
    )
    (net (code "74") (name "unconnected-(U$1-PadICSP2)") (class "Default")
      (node (ref "U$1") (pin "ICSP2") (pinfunction "ICSP2_ICSP2") (pintype "bidirectional"))
    )
    (net (code "75") (name "unconnected-(U$1-PadICSP3)") (class "Default")
      (node (ref "U$1") (pin "ICSP3") (pinfunction "ICSP3_ICSP3") (pintype "bidirectional"))
    )
    (net (code "76") (name "unconnected-(U$1-PadICSP4)") (class "Default")
      (node (ref "U$1") (pin "ICSP4") (pinfunction "ICSP4_ICSP4") (pintype "bidirectional"))
    )
    (net (code "77") (name "unconnected-(U$1-PadICSP5)") (class "Default")
      (node (ref "U$1") (pin "ICSP5") (pinfunction "ICSP5_ICSP5") (pintype "bidirectional"))
    )
    (net (code "78") (name "unconnected-(U$1-PadICSP6)") (class "Default")
      (node (ref "U$1") (pin "ICSP6") (pinfunction "ICSP6_ICSP6") (pintype "bidirectional"))
    )
    (net (code "79") (name "unconnected-(U$1-PadRAW)") (class "Default")
      (node (ref "U$1") (pin "RAW") (pinfunction "RAW_RAW") (pintype "bidirectional"))
    )
    (net (code "80") (name "unconnected-(U$1-PadRST)") (class "Default")
      (node (ref "U$1") (pin "RST") (pinfunction "RST_RST") (pintype "bidirectional"))
    )
    (net (code "81") (name "unconnected-(U$1-PadRST1)") (class "Default")
      (node (ref "U$1") (pin "RST1") (pinfunction "RST1_RST1") (pintype "bidirectional"))
    )
    (net (code "82") (name "unconnected-(U$1-PadRX1)") (class "Default")
      (node (ref "U$1") (pin "RX1") (pinfunction "RX1_RX1") (pintype "bidirectional"))
    )
    (net (code "83") (name "unconnected-(U$1-PadTX0)") (class "Default")
      (node (ref "U$1") (pin "TX0") (pinfunction "TX0_TX0") (pintype "bidirectional"))
    )
    (net (code "84") (name "unconnected-(U1-D2-Pad8)") (class "Default")
      (node (ref "U1") (pin "8") (pinfunction "D2_8") (pintype "bidirectional"))
    )
    (net (code "85") (name "unconnected-(U1-D3-Pad10)") (class "Default")
      (node (ref "U1") (pin "10") (pinfunction "D3_10") (pintype "bidirectional"))
    )
    (net (code "86") (name "unconnected-(U1-D4-Pad12)") (class "Default")
      (node (ref "U1") (pin "12") (pinfunction "D4_12") (pintype "bidirectional"))
    )
    (net (code "87") (name "unconnected-(U1-D5-Pad13)") (class "Default")
      (node (ref "U1") (pin "13") (pinfunction "D5_13") (pintype "bidirectional"))
    )
    (net (code "88") (name "unconnected-(U1-D6-Pad15)") (class "Default")
      (node (ref "U1") (pin "15") (pinfunction "D6_15") (pintype "bidirectional"))
    )
    (net (code "89") (name "unconnected-(U1-D7-Pad17)") (class "Default")
      (node (ref "U1") (pin "17") (pinfunction "D7_17") (pintype "bidirectional"))
    )
    (net (code "90") (name "unconnected-(U1-D8-Pad19)") (class "Default")
      (node (ref "U1") (pin "19") (pinfunction "D8_19") (pintype "bidirectional"))
    )
    (net (code "91") (name "unconnected-(U1-DOUT-Pad22)") (class "Default")
      (node (ref "U1") (pin "22") (pinfunction "DOUT_22") (pintype "output"))
    )
  )
)
